# pi-radio.net
KiCad netlist of a schematic drawn in EAGLE
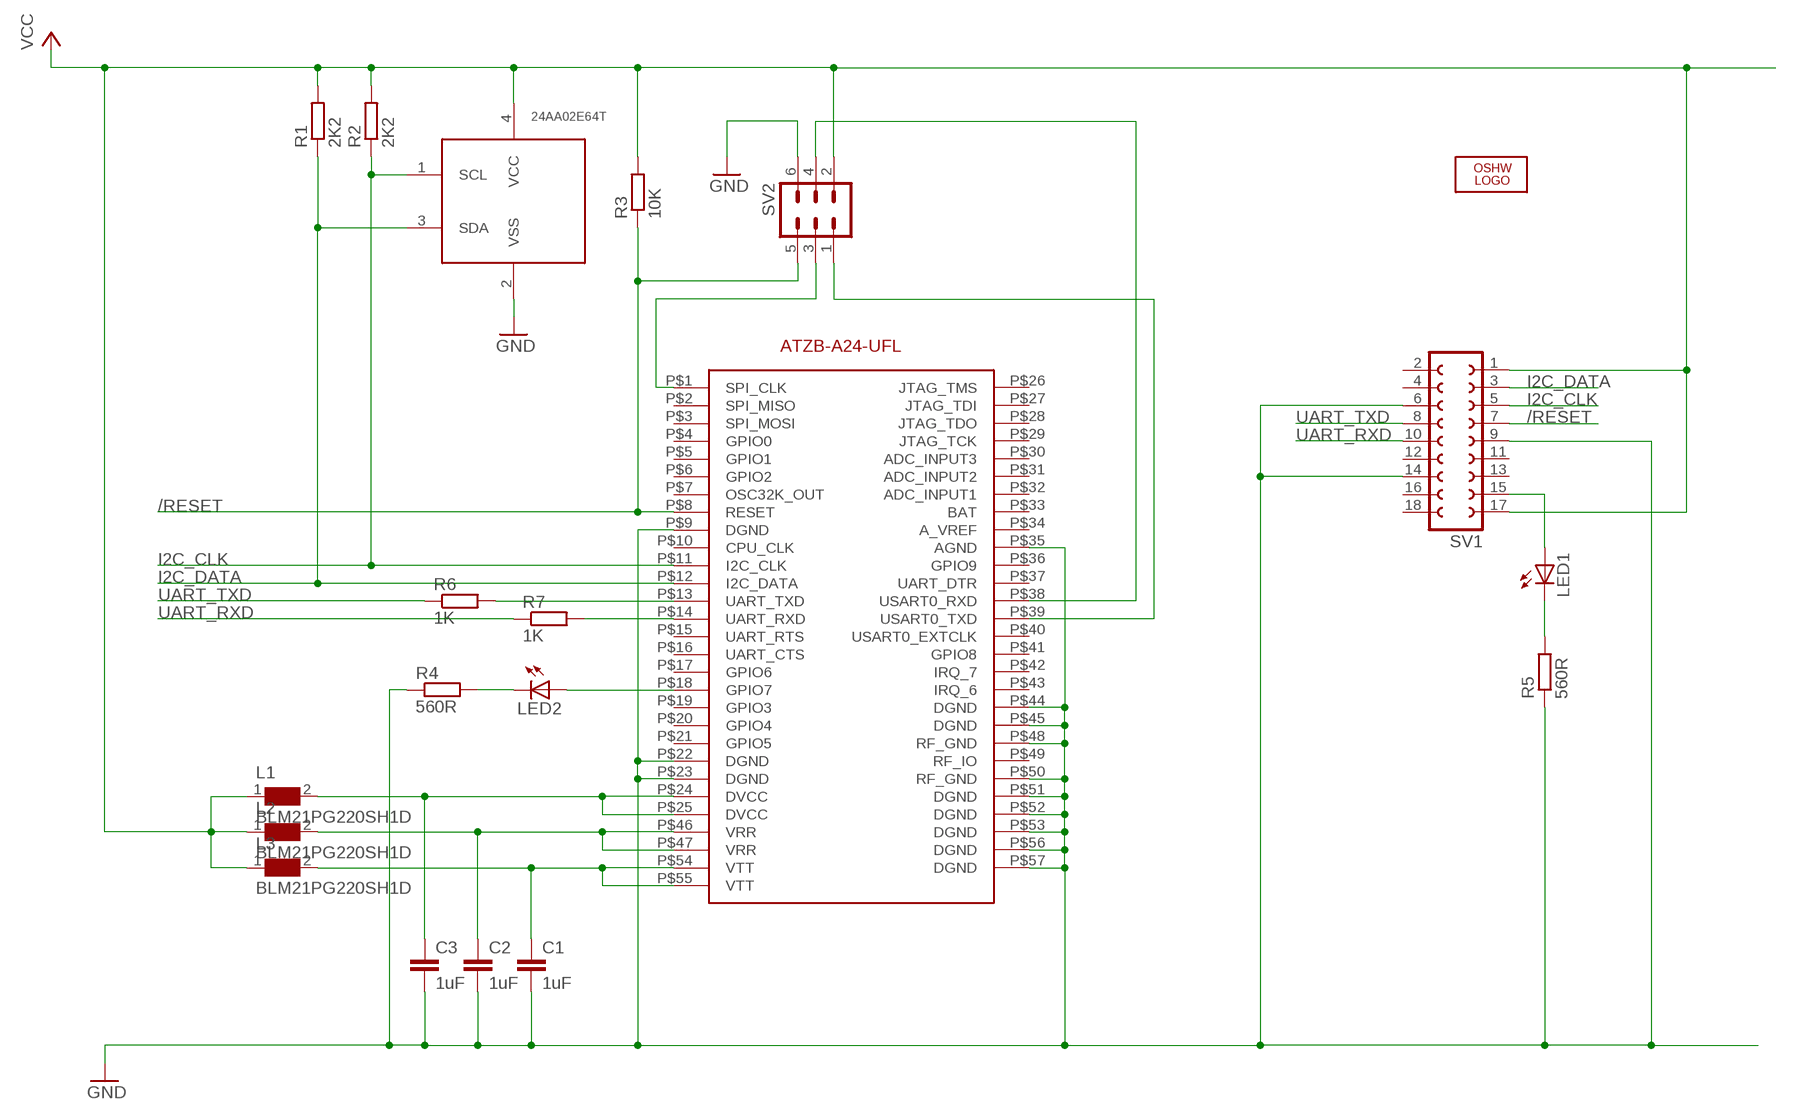
[diagram p0: schematic, sheet 1]

(export (version "E")
  (design (tool "Eeschema 10.0.6"))
  (components
    (comp (ref "C1")
      (value "1uF")
      (footprint "eagle-import:C0603")
      (libsource (lib "eagle-import") (part "C-EUC0603"))
    )
    (comp (ref "C2")
      (value "1uF")
      (footprint "eagle-import:C0603")
      (libsource (lib "eagle-import") (part "C-EUC0603"))
    )
    (comp (ref "C3")
      (value "1uF")
      (footprint "eagle-import:C0603")
      (libsource (lib "eagle-import") (part "C-EUC0603"))
    )
    (comp (ref "L1")
      (value "BLM21PG220SH1D")
      (footprint "eagle-import:0805")
      (libsource (lib "eagle-import") (part "WE-CBF_0805"))
    )
    (comp (ref "L2")
      (value "BLM21PG220SH1D")
      (footprint "eagle-import:0805")
      (libsource (lib "eagle-import") (part "WE-CBF_0805"))
    )
    (comp (ref "L3")
      (value "BLM21PG220SH1D")
      (footprint "eagle-import:0805")
      (libsource (lib "eagle-import") (part "WE-CBF_0805"))
    )
    (comp (ref "LED1")
      (value "LEDSML0805")
      (footprint "eagle-import:SML0805")
      (libsource (lib "eagle-import") (part "LEDSML0805"))
    )
    (comp (ref "LED2")
      (value "LEDSML0805")
      (footprint "eagle-import:SML0805")
      (libsource (lib "eagle-import") (part "LEDSML0805"))
    )
    (comp (ref "LOGO1")
      (value "OSHW_LOGO_8MILX0100-NT")
      (footprint "eagle-import:OSHW_8X100_NOTEXT")
      (libsource (lib "eagle-import") (part "OSHW_LOGO_8MILX0100-NT"))
    )
    (comp (ref "R1")
      (value "2K2")
      (footprint "eagle-import:R0603")
      (libsource (lib "eagle-import") (part "R-EU_R0603"))
    )
    (comp (ref "R2")
      (value "2K2")
      (footprint "eagle-import:R0603")
      (libsource (lib "eagle-import") (part "R-EU_R0603"))
    )
    (comp (ref "R3")
      (value "10K")
      (footprint "eagle-import:R0603")
      (libsource (lib "eagle-import") (part "R-EU_R0603"))
    )
    (comp (ref "R4")
      (value "560R")
      (footprint "eagle-import:R0603")
      (libsource (lib "eagle-import") (part "R-EU_R0603"))
    )
    (comp (ref "R5")
      (value "560R")
      (footprint "eagle-import:R0603")
      (libsource (lib "eagle-import") (part "R-EU_R0603"))
    )
    (comp (ref "R6")
      (value "1K")
      (footprint "eagle-import:R0603")
      (libsource (lib "eagle-import") (part "R-EU_R0603"))
    )
    (comp (ref "R7")
      (value "1K")
      (footprint "eagle-import:R0603")
      (libsource (lib "eagle-import") (part "R-EU_R0603"))
    )
    (comp (ref "SV1")
      (value "FE09-2")
      (footprint "eagle-import:FE09-2")
      (libsource (lib "eagle-import") (part "FE09-2"))
    )
    (comp (ref "SV2")
      (value "MA03-2")
      (footprint "eagle-import:MA03-2")
      (libsource (lib "eagle-import") (part "MA03-2"))
    )
    (comp (ref "U$1")
      (value "ATZB-A24-UFL")
      (footprint "eagle-import:ATZB-A24-UFL")
      (libsource (lib "eagle-import") (part "ATZB-A24-UFL"))
    )
    (comp (ref "U$2")
      (value "24AA02E64T")
      (footprint "eagle-import:SOT23-5L")
      (libsource (lib "eagle-import") (part "24AA02E64T"))
    )
  )
  (nets
    (net (code "1") (name "/I2C_CLK") (class "Default")
      (node (ref "R2") (pin "1") (pinfunction "1_1") (pintype "passive"))
      (node (ref "SV1") (pin "5") (pinfunction "5_5") (pintype "passive"))
      (node (ref "U$1") (pin "P$11") (pinfunction "I2C_CLK_P$11") (pintype "bidirectional"))
      (node (ref "U$2") (pin "1") (pinfunction "SCL_1") (pintype "bidirectional"))
    )
    (net (code "2") (name "/I2C_DATA") (class "Default")
      (node (ref "R1") (pin "1") (pinfunction "1_1") (pintype "passive"))
      (node (ref "SV1") (pin "3") (pinfunction "3_3") (pintype "passive"))
      (node (ref "U$1") (pin "P$12") (pinfunction "I2C_DATA_P$12") (pintype "bidirectional"))
      (node (ref "U$2") (pin "3") (pinfunction "SDA_3") (pintype "bidirectional"))
    )
    (net (code "3") (name "/UART_RXD") (class "Default")
      (node (ref "R7") (pin "1") (pinfunction "1_1") (pintype "passive"))
      (node (ref "SV1") (pin "10") (pinfunction "10_10") (pintype "passive"))
    )
    (net (code "4") (name "/UART_TXD") (class "Default")
      (node (ref "R6") (pin "1") (pinfunction "1_1") (pintype "passive"))
      (node (ref "SV1") (pin "8") (pinfunction "8_8") (pintype "passive"))
    )
    (net (code "5") (name "/{slash}RESET") (class "Default")
      (node (ref "R3") (pin "1") (pinfunction "1_1") (pintype "passive"))
      (node (ref "SV1") (pin "7") (pinfunction "7_7") (pintype "passive"))
      (node (ref "SV2") (pin "5") (pinfunction "5_5") (pintype "passive"))
      (node (ref "U$1") (pin "P$8") (pinfunction "RESET_P$8") (pintype "bidirectional"))
    )
    (net (code "6") (name "GND") (class "Default")
      (node (ref "C1") (pin "2") (pinfunction "2_2") (pintype "passive"))
      (node (ref "C2") (pin "2") (pinfunction "2_2") (pintype "passive"))
      (node (ref "C3") (pin "2") (pinfunction "2_2") (pintype "passive"))
      (node (ref "R4") (pin "1") (pinfunction "1_1") (pintype "passive"))
      (node (ref "R5") (pin "1") (pinfunction "1_1") (pintype "passive"))
      (node (ref "SV1") (pin "14") (pinfunction "14_14") (pintype "passive"))
      (node (ref "SV1") (pin "6") (pinfunction "6_6") (pintype "passive"))
      (node (ref "SV1") (pin "9") (pinfunction "9_9") (pintype "passive"))
      (node (ref "SV2") (pin "6") (pinfunction "6_6") (pintype "passive"))
      (node (ref "U$1") (pin "P$22") (pinfunction "DGND_P$22") (pintype "bidirectional"))
      (node (ref "U$1") (pin "P$23") (pinfunction "DGND_P$23") (pintype "bidirectional"))
      (node (ref "U$1") (pin "P$35") (pinfunction "AGND_P$35") (pintype "bidirectional"))
      (node (ref "U$1") (pin "P$44") (pinfunction "DGND_P$44") (pintype "bidirectional"))
      (node (ref "U$1") (pin "P$45") (pinfunction "DGND_P$45") (pintype "bidirectional"))
      (node (ref "U$1") (pin "P$48") (pinfunction "RF_GND_P$48") (pintype "bidirectional"))
      (node (ref "U$1") (pin "P$50") (pinfunction "RF_GND_P$50") (pintype "bidirectional"))
      (node (ref "U$1") (pin "P$51") (pinfunction "DGND_P$51") (pintype "bidirectional"))
      (node (ref "U$1") (pin "P$52") (pinfunction "DGND_P$52") (pintype "bidirectional"))
      (node (ref "U$1") (pin "P$53") (pinfunction "DGND_P$53") (pintype "bidirectional"))
      (node (ref "U$1") (pin "P$56") (pinfunction "DGND_P$56") (pintype "bidirectional"))
      (node (ref "U$1") (pin "P$57") (pinfunction "DGND_P$57") (pintype "bidirectional"))
      (node (ref "U$1") (pin "P$9") (pinfunction "DGND_P$9") (pintype "bidirectional"))
      (node (ref "U$2") (pin "2") (pinfunction "VSS_2") (pintype "bidirectional"))
    )
    (net (code "7") (name "Net-(C1-Pad1)") (class "Default")
      (node (ref "C1") (pin "1") (pinfunction "1_1") (pintype "passive"))
      (node (ref "L3") (pin "2") (pinfunction "2_2") (pintype "passive"))
      (node (ref "U$1") (pin "P$54") (pinfunction "VTT_P$54") (pintype "bidirectional"))
      (node (ref "U$1") (pin "P$55") (pinfunction "VTT_P$55") (pintype "bidirectional"))
    )
    (net (code "8") (name "Net-(C2-Pad1)") (class "Default")
      (node (ref "C2") (pin "1") (pinfunction "1_1") (pintype "passive"))
      (node (ref "L2") (pin "2") (pinfunction "2_2") (pintype "passive"))
      (node (ref "U$1") (pin "P$46") (pinfunction "VRR_P$46") (pintype "bidirectional"))
      (node (ref "U$1") (pin "P$47") (pinfunction "VRR_P$47") (pintype "bidirectional"))
    )
    (net (code "9") (name "Net-(C3-Pad1)") (class "Default")
      (node (ref "C3") (pin "1") (pinfunction "1_1") (pintype "passive"))
      (node (ref "L1") (pin "2") (pinfunction "2_2") (pintype "passive"))
      (node (ref "U$1") (pin "P$24") (pinfunction "DVCC_P$24") (pintype "bidirectional"))
      (node (ref "U$1") (pin "P$25") (pinfunction "DVCC_P$25") (pintype "bidirectional"))
    )
    (net (code "10") (name "Net-(LED1-PadA)") (class "Default")
      (node (ref "LED1") (pin "A") (pinfunction "A_A") (pintype "passive"))
      (node (ref "SV1") (pin "15") (pinfunction "15_15") (pintype "passive"))
    )
    (net (code "11") (name "Net-(LED1-PadC)") (class "Default")
      (node (ref "LED1") (pin "C") (pinfunction "C_C") (pintype "passive"))
      (node (ref "R5") (pin "2") (pinfunction "2_2") (pintype "passive"))
    )
    (net (code "12") (name "Net-(LED2-PadC)") (class "Default")
      (node (ref "LED2") (pin "C") (pinfunction "C_C") (pintype "passive"))
      (node (ref "R4") (pin "2") (pinfunction "2_2") (pintype "passive"))
    )
    (net (code "13") (name "Net-(U$1-GPIO7)") (class "Default")
      (node (ref "LED2") (pin "A") (pinfunction "A_A") (pintype "passive"))
      (node (ref "U$1") (pin "P$18") (pinfunction "GPIO7_P$18") (pintype "bidirectional"))
    )
    (net (code "14") (name "Net-(U$1-SPI_CLK)") (class "Default")
      (node (ref "SV2") (pin "3") (pinfunction "3_3") (pintype "passive"))
      (node (ref "U$1") (pin "P$1") (pinfunction "SPI_CLK_P$1") (pintype "bidirectional"))
    )
    (net (code "15") (name "Net-(U$1-UART_RXD)") (class "Default")
      (node (ref "R7") (pin "2") (pinfunction "2_2") (pintype "passive"))
      (node (ref "U$1") (pin "P$14") (pinfunction "UART_RXD_P$14") (pintype "bidirectional"))
    )
    (net (code "16") (name "Net-(U$1-UART_TXD)") (class "Default")
      (node (ref "R6") (pin "2") (pinfunction "2_2") (pintype "passive"))
      (node (ref "U$1") (pin "P$13") (pinfunction "UART_TXD_P$13") (pintype "bidirectional"))
    )
    (net (code "17") (name "Net-(U$1-USART0_RXD)") (class "Default")
      (node (ref "SV2") (pin "4") (pinfunction "4_4") (pintype "passive"))
      (node (ref "U$1") (pin "P$38") (pinfunction "USART0_RXD_P$38") (pintype "bidirectional"))
    )
    (net (code "18") (name "Net-(U$1-USART0_TXD)") (class "Default")
      (node (ref "SV2") (pin "1") (pinfunction "1_1") (pintype "passive"))
      (node (ref "U$1") (pin "P$39") (pinfunction "USART0_TXD_P$39") (pintype "bidirectional"))
    )
    (net (code "19") (name "VCC") (class "Default")
      (node (ref "L1") (pin "1") (pinfunction "1_1") (pintype "passive"))
      (node (ref "L2") (pin "1") (pinfunction "1_1") (pintype "passive"))
      (node (ref "L3") (pin "1") (pinfunction "1_1") (pintype "passive"))
      (node (ref "R1") (pin "2") (pinfunction "2_2") (pintype "passive"))
      (node (ref "R2") (pin "2") (pinfunction "2_2") (pintype "passive"))
      (node (ref "R3") (pin "2") (pinfunction "2_2") (pintype "passive"))
      (node (ref "SV1") (pin "1") (pinfunction "1_1") (pintype "passive"))
      (node (ref "SV1") (pin "17") (pinfunction "17_17") (pintype "passive"))
      (node (ref "SV2") (pin "2") (pinfunction "2_2") (pintype "passive"))
      (node (ref "U$2") (pin "4") (pinfunction "VCC_4") (pintype "bidirectional"))
    )
    (net (code "20") (name "unconnected-(SV1-Pad2)") (class "Default")
      (node (ref "SV1") (pin "2") (pinfunction "2_2") (pintype "passive"))
    )
    (net (code "21") (name "unconnected-(SV1-Pad4)") (class "Default")
      (node (ref "SV1") (pin "4") (pinfunction "4_4") (pintype "passive"))
    )
    (net (code "22") (name "unconnected-(SV1-Pad11)") (class "Default")
      (node (ref "SV1") (pin "11") (pinfunction "11_11") (pintype "passive"))
    )
    (net (code "23") (name "unconnected-(SV1-Pad12)") (class "Default")
      (node (ref "SV1") (pin "12") (pinfunction "12_12") (pintype "passive"))
    )
    (net (code "24") (name "unconnected-(SV1-Pad13)") (class "Default")
      (node (ref "SV1") (pin "13") (pinfunction "13_13") (pintype "passive"))
    )
    (net (code "25") (name "unconnected-(SV1-Pad16)") (class "Default")
      (node (ref "SV1") (pin "16") (pinfunction "16_16") (pintype "passive"))
    )
    (net (code "26") (name "unconnected-(SV1-Pad18)") (class "Default")
      (node (ref "SV1") (pin "18") (pinfunction "18_18") (pintype "passive"))
    )
    (net (code "27") (name "unconnected-(U$1-ADC_INPUT1-PadP$32)") (class "Default")
      (node (ref "U$1") (pin "P$32") (pinfunction "ADC_INPUT1_P$32") (pintype "bidirectional"))
    )
    (net (code "28") (name "unconnected-(U$1-ADC_INPUT2-PadP$31)") (class "Default")
      (node (ref "U$1") (pin "P$31") (pinfunction "ADC_INPUT2_P$31") (pintype "bidirectional"))
    )
    (net (code "29") (name "unconnected-(U$1-ADC_INPUT3-PadP$30)") (class "Default")
      (node (ref "U$1") (pin "P$30") (pinfunction "ADC_INPUT3_P$30") (pintype "bidirectional"))
    )
    (net (code "30") (name "unconnected-(U$1-A_VREF-PadP$34)") (class "Default")
      (node (ref "U$1") (pin "P$34") (pinfunction "A_VREF_P$34") (pintype "bidirectional"))
    )
    (net (code "31") (name "unconnected-(U$1-BAT-PadP$33)") (class "Default")
      (node (ref "U$1") (pin "P$33") (pinfunction "BAT_P$33") (pintype "bidirectional"))
    )
    (net (code "32") (name "unconnected-(U$1-CPU_CLK-PadP$10)") (class "Default")
      (node (ref "U$1") (pin "P$10") (pinfunction "CPU_CLK_P$10") (pintype "bidirectional"))
    )
    (net (code "33") (name "unconnected-(U$1-GPIO0-PadP$4)") (class "Default")
      (node (ref "U$1") (pin "P$4") (pinfunction "GPIO0_P$4") (pintype "bidirectional"))
    )
    (net (code "34") (name "unconnected-(U$1-GPIO1-PadP$5)") (class "Default")
      (node (ref "U$1") (pin "P$5") (pinfunction "GPIO1_P$5") (pintype "bidirectional"))
    )
    (net (code "35") (name "unconnected-(U$1-GPIO2-PadP$6)") (class "Default")
      (node (ref "U$1") (pin "P$6") (pinfunction "GPIO2_P$6") (pintype "bidirectional"))
    )
    (net (code "36") (name "unconnected-(U$1-GPIO3-PadP$19)") (class "Default")
      (node (ref "U$1") (pin "P$19") (pinfunction "GPIO3_P$19") (pintype "bidirectional"))
    )
    (net (code "37") (name "unconnected-(U$1-GPIO4-PadP$20)") (class "Default")
      (node (ref "U$1") (pin "P$20") (pinfunction "GPIO4_P$20") (pintype "bidirectional"))
    )
    (net (code "38") (name "unconnected-(U$1-GPIO5-PadP$21)") (class "Default")
      (node (ref "U$1") (pin "P$21") (pinfunction "GPIO5_P$21") (pintype "bidirectional"))
    )
    (net (code "39") (name "unconnected-(U$1-GPIO6-PadP$17)") (class "Default")
      (node (ref "U$1") (pin "P$17") (pinfunction "GPIO6_P$17") (pintype "bidirectional"))
    )
    (net (code "40") (name "unconnected-(U$1-GPIO8-PadP$41)") (class "Default")
      (node (ref "U$1") (pin "P$41") (pinfunction "GPIO8_P$41") (pintype "bidirectional"))
    )
    (net (code "41") (name "unconnected-(U$1-GPIO9-PadP$36)") (class "Default")
      (node (ref "U$1") (pin "P$36") (pinfunction "GPIO9_P$36") (pintype "bidirectional"))
    )
    (net (code "42") (name "unconnected-(U$1-IRQ_6-PadP$43)") (class "Default")
      (node (ref "U$1") (pin "P$43") (pinfunction "IRQ_6_P$43") (pintype "bidirectional"))
    )
    (net (code "43") (name "unconnected-(U$1-IRQ_7-PadP$42)") (class "Default")
      (node (ref "U$1") (pin "P$42") (pinfunction "IRQ_7_P$42") (pintype "bidirectional"))
    )
    (net (code "44") (name "unconnected-(U$1-JTAG_TCK-PadP$29)") (class "Default")
      (node (ref "U$1") (pin "P$29") (pinfunction "JTAG_TCK_P$29") (pintype "bidirectional"))
    )
    (net (code "45") (name "unconnected-(U$1-JTAG_TDI-PadP$27)") (class "Default")
      (node (ref "U$1") (pin "P$27") (pinfunction "JTAG_TDI_P$27") (pintype "bidirectional"))
    )
    (net (code "46") (name "unconnected-(U$1-JTAG_TDO-PadP$28)") (class "Default")
      (node (ref "U$1") (pin "P$28") (pinfunction "JTAG_TDO_P$28") (pintype "bidirectional"))
    )
    (net (code "47") (name "unconnected-(U$1-JTAG_TMS-PadP$26)") (class "Default")
      (node (ref "U$1") (pin "P$26") (pinfunction "JTAG_TMS_P$26") (pintype "bidirectional"))
    )
    (net (code "48") (name "unconnected-(U$1-OSC32K_OUT-PadP$7)") (class "Default")
      (node (ref "U$1") (pin "P$7") (pinfunction "OSC32K_OUT_P$7") (pintype "bidirectional"))
    )
    (net (code "49") (name "unconnected-(U$1-RF_IO-PadP$49)") (class "Default")
      (node (ref "U$1") (pin "P$49") (pinfunction "RF_IO_P$49") (pintype "bidirectional"))
    )
    (net (code "50") (name "unconnected-(U$1-SPI_MISO-PadP$2)") (class "Default")
      (node (ref "U$1") (pin "P$2") (pinfunction "SPI_MISO_P$2") (pintype "bidirectional"))
    )
    (net (code "51") (name "unconnected-(U$1-SPI_MOSI-PadP$3)") (class "Default")
      (node (ref "U$1") (pin "P$3") (pinfunction "SPI_MOSI_P$3") (pintype "bidirectional"))
    )
    (net (code "52") (name "unconnected-(U$1-UART_CTS-PadP$16)") (class "Default")
      (node (ref "U$1") (pin "P$16") (pinfunction "UART_CTS_P$16") (pintype "bidirectional"))
    )
    (net (code "53") (name "unconnected-(U$1-UART_DTR-PadP$37)") (class "Default")
      (node (ref "U$1") (pin "P$37") (pinfunction "UART_DTR_P$37") (pintype "bidirectional"))
    )
    (net (code "54") (name "unconnected-(U$1-UART_RTS-PadP$15)") (class "Default")
      (node (ref "U$1") (pin "P$15") (pinfunction "UART_RTS_P$15") (pintype "bidirectional"))
    )
    (net (code "55") (name "unconnected-(U$1-USART0_EXTCLK-PadP$40)") (class "Default")
      (node (ref "U$1") (pin "P$40") (pinfunction "USART0_EXTCLK_P$40") (pintype "bidirectional"))
    )
  )
)
